# OSP_Carrier_V7_Release_DJB.net
KiCad netlist of a schematic drawn in Altium Designer
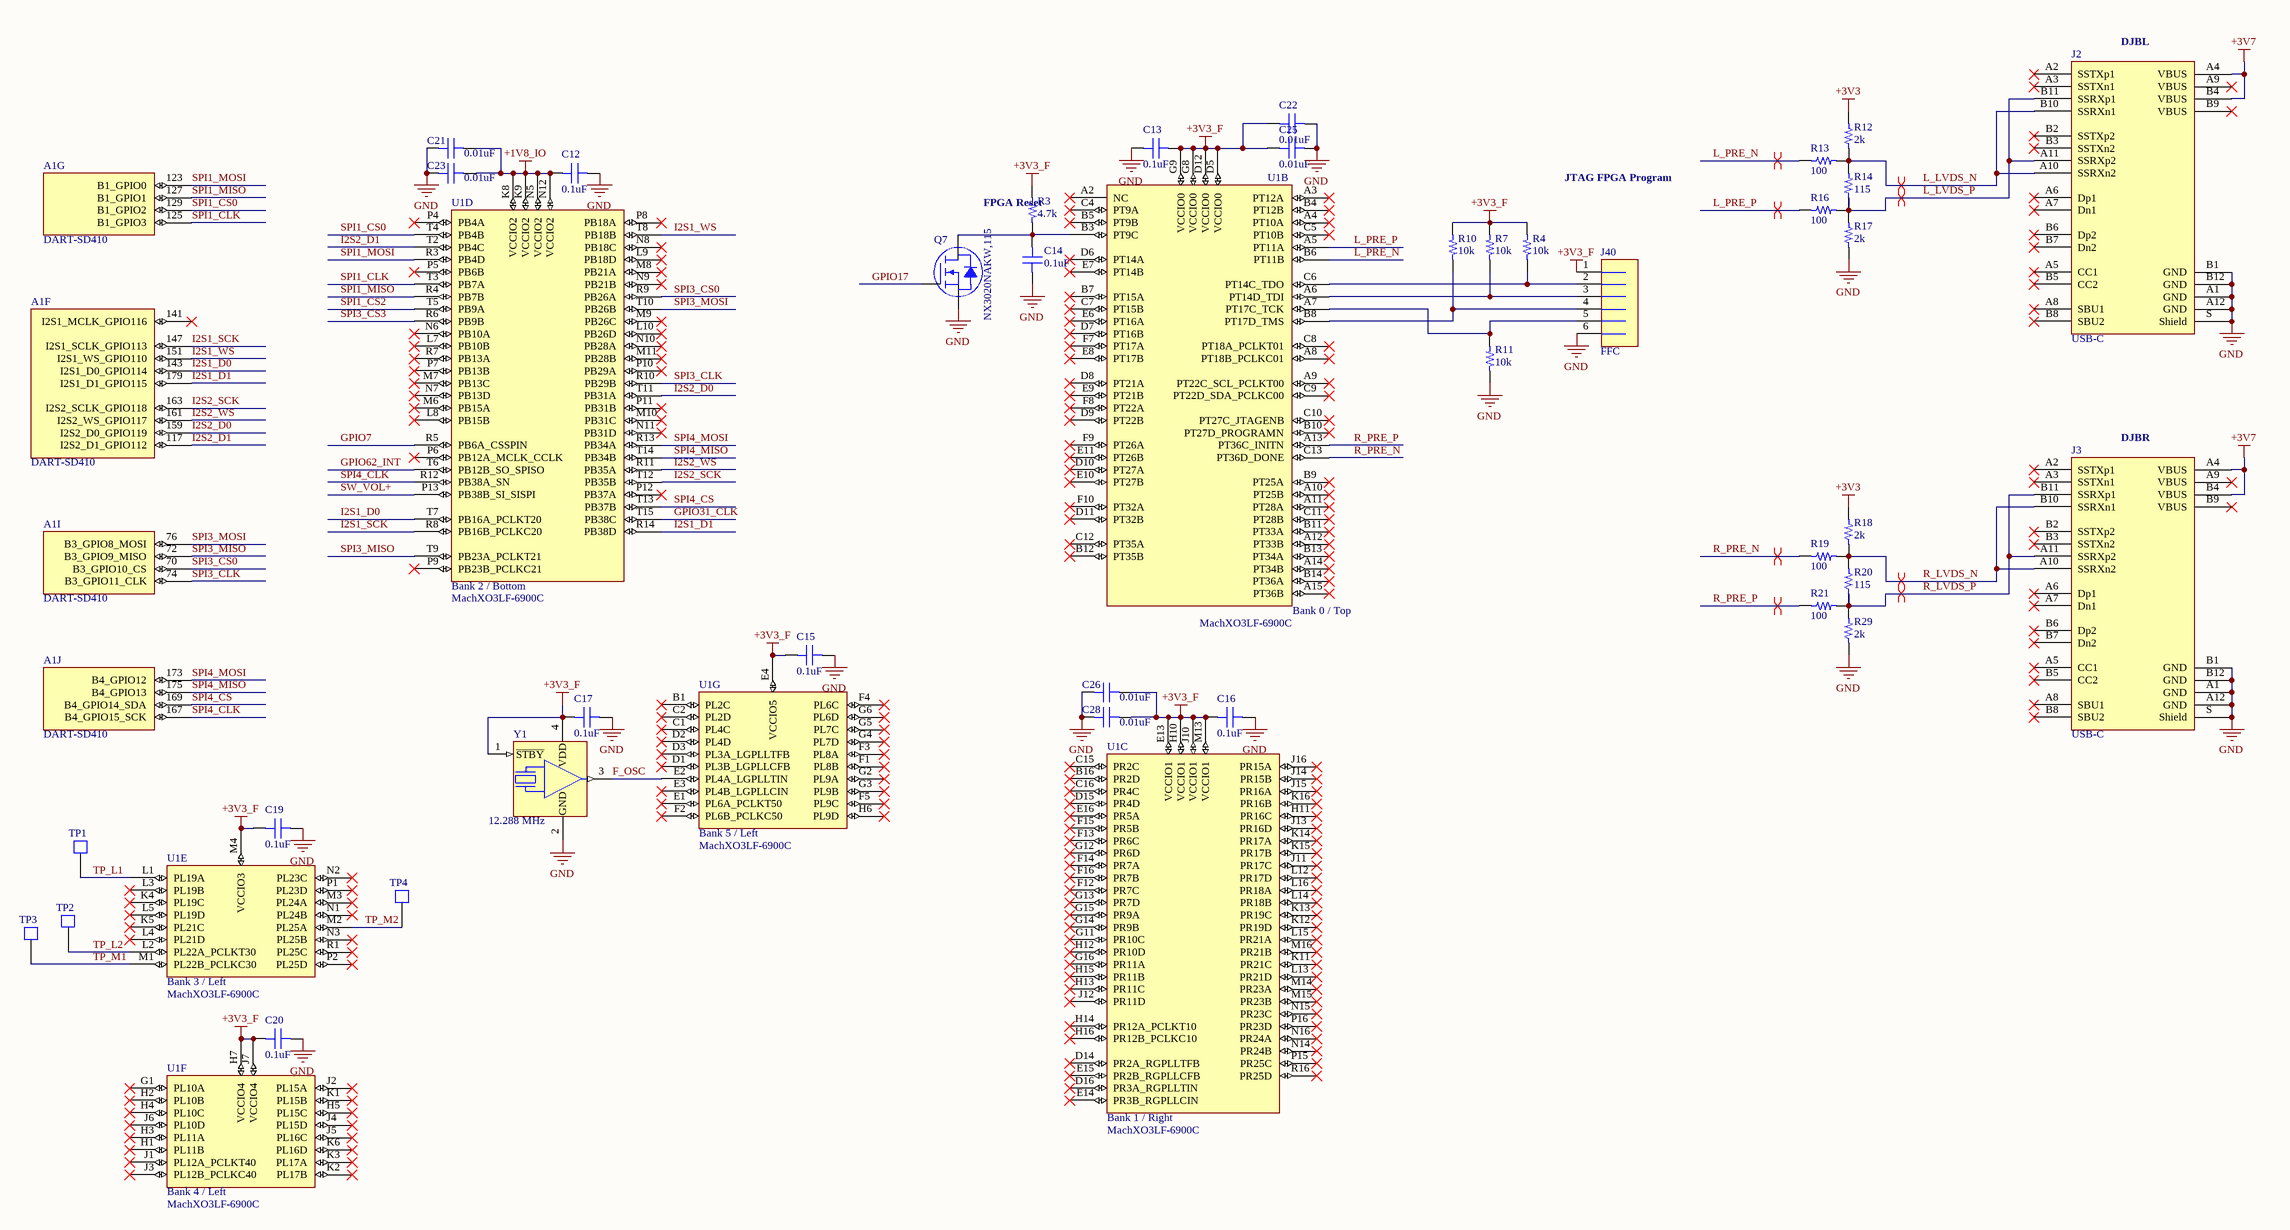
[diagram p0: OSP_Carrier_V7_Release_DJB.SchDoc]

(export (version "E")
  (design (tool "Eeschema 10.0.6"))
  (components
    (comp (ref "A1")
      (value "DART-SD410")
      (footprint "DART-SD410")
      (description "Variscite DART-SD410 System on Module")
      (libsource (lib "DART-SD410") (part "DART-SD410"))
    )
    (comp (ref "C12")
      (value "0.1uF")
      (footprint "CAP 0402/1005")
      (description "CAP CER 0.1UF 50V X7R 0402")
      (fields
        (field (name "PART NUMBER") "C1005X7R1H104K050BB")
        (field (name "MANUFACTURER") "TDK Corporation")
      )
      (libsource (lib "Celestial Library Database") (part "Capacitor"))
    )
    (comp (ref "C13")
      (value "0.1uF")
      (footprint "CAP 0402/1005")
      (description "CAP CER 0.1UF 50V X7R 0402")
      (fields
        (field (name "PART NUMBER") "C1005X7R1H104K050BB")
        (field (name "MANUFACTURER") "TDK Corporation")
      )
      (libsource (lib "Celestial Library Database") (part "Capacitor"))
    )
    (comp (ref "C14")
      (value "0.1uF")
      (footprint "CAP 0402/1005")
      (description "CAP CER 0.1UF 50V X7R 0402")
      (fields
        (field (name "PART NUMBER") "C1005X7R1H104K050BB")
        (field (name "MANUFACTURER") "TDK Corporation")
      )
      (libsource (lib "Celestial Library Database") (part "Capacitor"))
    )
    (comp (ref "C15")
      (value "0.1uF")
      (footprint "CAP 0402/1005")
      (description "CAP CER 0.1UF 50V X7R 0402")
      (fields
        (field (name "PART NUMBER") "C1005X7R1H104K050BB")
        (field (name "MANUFACTURER") "TDK Corporation")
      )
      (libsource (lib "Celestial Library Database") (part "Capacitor"))
    )
    (comp (ref "C16")
      (value "0.1uF")
      (footprint "CAP 0402/1005")
      (description "CAP CER 0.1UF 50V X7R 0402")
      (fields
        (field (name "PART NUMBER") "C1005X7R1H104K050BB")
        (field (name "MANUFACTURER") "TDK Corporation")
      )
      (libsource (lib "Celestial Library Database") (part "Capacitor"))
    )
    (comp (ref "C17")
      (value "0.1uF")
      (footprint "CAP 0402/1005")
      (description "CAP CER 0.1UF 50V X7R 0402")
      (fields
        (field (name "PART NUMBER") "C1005X7R1H104K050BB")
        (field (name "MANUFACTURER") "TDK Corporation")
      )
      (libsource (lib "Celestial Library Database") (part "Capacitor"))
    )
    (comp (ref "C19")
      (value "0.1uF")
      (footprint "CAP 0402/1005")
      (description "CAP CER 0.1UF 50V X7R 0402")
      (fields
        (field (name "PART NUMBER") "C1005X7R1H104K050BB")
        (field (name "MANUFACTURER") "TDK Corporation")
      )
      (libsource (lib "Celestial Library Database") (part "Capacitor"))
    )
    (comp (ref "C20")
      (value "0.1uF")
      (footprint "CAP 0402/1005")
      (description "CAP CER 0.1UF 50V X7R 0402")
      (fields
        (field (name "PART NUMBER") "C1005X7R1H104K050BB")
        (field (name "MANUFACTURER") "TDK Corporation")
      )
      (libsource (lib "Celestial Library Database") (part "Capacitor"))
    )
    (comp (ref "C21")
      (value "0.01uF")
      (footprint "CAP 0402/1005")
      (description "CAP CER 10000PF 25V X7R 0402")
      (fields (field (name "PART NUMBER") "CC0402KRX7R8BB103") (field (name "MANUFACTURER") "Yageo"))
      (libsource (lib "Celestial Library Database") (part "Capacitor"))
    )
    (comp (ref "C22")
      (value "0.01uF")
      (footprint "CAP 0402/1005")
      (description "CAP CER 10000PF 25V X7R 0402")
      (fields (field (name "PART NUMBER") "CC0402KRX7R8BB103") (field (name "MANUFACTURER") "Yageo"))
      (libsource (lib "Celestial Library Database") (part "Capacitor"))
    )
    (comp (ref "C23")
      (value "0.01uF")
      (footprint "CAP 0402/1005")
      (description "CAP CER 10000PF 25V X7R 0402")
      (fields (field (name "PART NUMBER") "CC0402KRX7R8BB103") (field (name "MANUFACTURER") "Yageo"))
      (libsource (lib "Celestial Library Database") (part "Capacitor"))
    )
    (comp (ref "C25")
      (value "0.01uF")
      (footprint "CAP 0402/1005")
      (description "CAP CER 10000PF 25V X7R 0402")
      (fields (field (name "PART NUMBER") "CC0402KRX7R8BB103") (field (name "MANUFACTURER") "Yageo"))
      (libsource (lib "Celestial Library Database") (part "Capacitor"))
    )
    (comp (ref "C26")
      (value "0.01uF")
      (footprint "CAP 0402/1005")
      (description "CAP CER 10000PF 25V X7R 0402")
      (fields (field (name "PART NUMBER") "CC0402KRX7R8BB103") (field (name "MANUFACTURER") "Yageo"))
      (libsource (lib "Celestial Library Database") (part "Capacitor"))
    )
    (comp (ref "C28")
      (value "0.01uF")
      (footprint "CAP 0402/1005")
      (description "CAP CER 10000PF 25V X7R 0402")
      (fields (field (name "PART NUMBER") "CC0402KRX7R8BB103") (field (name "MANUFACTURER") "Yageo"))
      (libsource (lib "Celestial Library Database") (part "Capacitor"))
    )
    (comp (ref "J2")
      (value "USB-C")
      (footprint "TE_USB-C_2129691-1")
      (description "TE 2129691-1 USB-C Socket")
      (libsource (lib "OSP_Symbols") (part "TE_USB_C_2129691-1"))
    )
    (comp (ref "J3")
      (value "USB-C")
      (footprint "TE_USB-C_2129691-1")
      (description "TE 2129691-1 USB-C Socket")
      (libsource (lib "OSP_Symbols") (part "TE_USB_C_2129691-1"))
    )
    (comp (ref "J40")
      (value "FFC")
      (footprint "AMPHENOL_HFW6R-1STE1LF")
      (description "Amphenol HFW6R-1STE1LF 6-pin flat flexible cable connector")
      (libsource (lib "OSP_Symbols") (part "AMPHENOL_HFW6R-1STE1LF"))
    )
    (comp (ref "Q7")
      (value "NX3020NAKW,115")
      (footprint "NXP SOT-323-3")
      (description "MOSFET N-CH 30V 180MA SOT323")
      (libsource (lib "Celestial Library Database") (part "NXP MOSFET N-CH SOT-23-3"))
    )
    (comp (ref "R3")
      (value "4.7k")
      (footprint "RES 0402/1005")
      (description "RES SMD 4.7K OHM 1% 1/10W 0402")
      (fields
        (field (name "PART NUMBER") "ERJ-2RKF4701X")
        (field (name "MANUFACTURER") "Panasonic Electronic Components")
      )
      (libsource (lib "Celestial Library Database") (part "Resistor"))
    )
    (comp (ref "R4")
      (value "10k")
      (footprint "RES 0402/1005")
      (description "RES SMD 10K OHM 1% 1/10W 0402")
      (fields
        (field (name "PART NUMBER") "ERJ-2RKF1002X")
        (field (name "MANUFACTURER") "Panasonic Electronic Components")
      )
      (libsource (lib "Celestial Library Database") (part "Resistor"))
    )
    (comp (ref "R7")
      (value "10k")
      (footprint "RES 0402/1005")
      (description "RES SMD 10K OHM 1% 1/10W 0402")
      (fields
        (field (name "PART NUMBER") "ERJ-2RKF1002X")
        (field (name "MANUFACTURER") "Panasonic Electronic Components")
      )
      (libsource (lib "Celestial Library Database") (part "Resistor"))
    )
    (comp (ref "R10")
      (value "10k")
      (footprint "RES 0402/1005")
      (description "RES SMD 10K OHM 1% 1/10W 0402")
      (fields
        (field (name "PART NUMBER") "ERJ-2RKF1002X")
        (field (name "MANUFACTURER") "Panasonic Electronic Components")
      )
      (libsource (lib "Celestial Library Database") (part "Resistor"))
    )
    (comp (ref "R11")
      (value "10k")
      (footprint "RES 0402/1005")
      (description "RES SMD 10K OHM 1% 1/10W 0402")
      (fields
        (field (name "PART NUMBER") "ERJ-2RKF1002X")
        (field (name "MANUFACTURER") "Panasonic Electronic Components")
      )
      (libsource (lib "Celestial Library Database") (part "Resistor"))
    )
    (comp (ref "R12")
      (value "2k")
      (footprint "RES 0402/1005")
      (description "RES SMD 2K OHM 1% 1/10W 0402")
      (fields
        (field (name "PART NUMBER") "ERJ-2RKF2001X")
        (field (name "MANUFACTURER") "Panasonic Electronic Components")
      )
      (libsource (lib "Celestial Library Database") (part "Resistor"))
    )
    (comp (ref "R13")
      (value "100")
      (footprint "RES 0402/1005")
      (description "RES SMD 100 OHM 1% 1/10W 0402")
      (fields
        (field (name "PART NUMBER") "ERJ-2RKF1000X")
        (field (name "MANUFACTURER") "Panasonic Electronic Components")
      )
      (libsource (lib "Celestial Library Database") (part "Resistor"))
    )
    (comp (ref "R14")
      (value "115")
      (footprint "RES 0402/1005")
      (description "RES SMD 115 OHM 1% 1/10W 0402")
      (fields
        (field (name "PART NUMBER") "ERJ-2RKF1150X")
        (field (name "MANUFACTURER") "Panasonic Electronic Components")
      )
      (libsource (lib "Celestial Library Database") (part "Resistor"))
    )
    (comp (ref "R16")
      (value "100")
      (footprint "RES 0402/1005")
      (description "RES SMD 100 OHM 1% 1/10W 0402")
      (fields
        (field (name "PART NUMBER") "ERJ-2RKF1000X")
        (field (name "MANUFACTURER") "Panasonic Electronic Components")
      )
      (libsource (lib "Celestial Library Database") (part "Resistor"))
    )
    (comp (ref "R17")
      (value "2k")
      (footprint "RES 0402/1005")
      (description "RES SMD 2K OHM 1% 1/10W 0402")
      (fields
        (field (name "PART NUMBER") "ERJ-2RKF2001X")
        (field (name "MANUFACTURER") "Panasonic Electronic Components")
      )
      (libsource (lib "Celestial Library Database") (part "Resistor"))
    )
    (comp (ref "R18")
      (value "2k")
      (footprint "RES 0402/1005")
      (description "RES SMD 2K OHM 1% 1/10W 0402")
      (fields
        (field (name "PART NUMBER") "ERJ-2RKF2001X")
        (field (name "MANUFACTURER") "Panasonic Electronic Components")
      )
      (libsource (lib "Celestial Library Database") (part "Resistor"))
    )
    (comp (ref "R19")
      (value "100")
      (footprint "RES 0402/1005")
      (description "RES SMD 100 OHM 1% 1/10W 0402")
      (fields
        (field (name "PART NUMBER") "ERJ-2RKF1000X")
        (field (name "MANUFACTURER") "Panasonic Electronic Components")
      )
      (libsource (lib "Celestial Library Database") (part "Resistor"))
    )
    (comp (ref "R20")
      (value "115")
      (footprint "RES 0402/1005")
      (description "RES SMD 115 OHM 1% 1/10W 0402")
      (fields
        (field (name "PART NUMBER") "ERJ-2RKF1150X")
        (field (name "MANUFACTURER") "Panasonic Electronic Components")
      )
      (libsource (lib "Celestial Library Database") (part "Resistor"))
    )
    (comp (ref "R21")
      (value "100")
      (footprint "RES 0402/1005")
      (description "RES SMD 100 OHM 1% 1/10W 0402")
      (fields
        (field (name "PART NUMBER") "ERJ-2RKF1000X")
        (field (name "MANUFACTURER") "Panasonic Electronic Components")
      )
      (libsource (lib "Celestial Library Database") (part "Resistor"))
    )
    (comp (ref "R29")
      (value "2k")
      (footprint "RES 0402/1005")
      (description "RES SMD 2K OHM 1% 1/10W 0402")
      (fields
        (field (name "PART NUMBER") "ERJ-2RKF2001X")
        (field (name "MANUFACTURER") "Panasonic Electronic Components")
      )
      (libsource (lib "Celestial Library Database") (part "Resistor"))
    )
    (comp (ref "TP1")
      (value "TP_SMD_1MM_SQ")
      (footprint "TP_SMD_1MM_SQ")
      (description "1mm Square SMD Test Point")
      (libsource (lib "OSP_Symbols") (part "TP_SMD_1MM_SQ"))
    )
    (comp (ref "TP2")
      (value "TP_SMD_1MM_SQ")
      (footprint "TP_SMD_1MM_SQ")
      (description "1mm Square SMD Test Point")
      (libsource (lib "OSP_Symbols") (part "TP_SMD_1MM_SQ"))
    )
    (comp (ref "TP3")
      (value "TP_SMD_1MM_SQ")
      (footprint "TP_SMD_1MM_SQ")
      (description "1mm Square SMD Test Point")
      (libsource (lib "OSP_Symbols") (part "TP_SMD_1MM_SQ"))
    )
    (comp (ref "TP4")
      (value "TP_SMD_1MM_SQ")
      (footprint "TP_SMD_1MM_SQ")
      (description "1mm Square SMD Test Point")
      (libsource (lib "OSP_Symbols") (part "TP_SMD_1MM_SQ"))
    )
    (comp (ref "U1")
      (value "MachXO3LF-6900C")
      (footprint "LCMXO3_caBGA_BG256")
      (description "Lattice MachXO3LF-6900C-5BG256C FPGA")
      (libsource (lib "OSP_Symbols") (part "LCMXO3LF-6900C-XBG256X"))
    )
    (comp (ref "Y1")
      (value "12.288 MHz")
      (footprint "OSC_2.5x2.0mm")
      (description "Microchip 12.288 MHz SMD MEMS Oscillator")
      (libsource (lib "OSP_Symbols") (part "MC_DSC1033DI2-012.2880"))
    )
  )
  (nets
    (net (code "1") (name "+1V8_IO") (class "Default")
      (node (ref "C12") (pin "2") (pinfunction "2_2") (pintype "passive"))
      (node (ref "C21") (pin "1") (pinfunction "1_1") (pintype "passive"))
      (node (ref "C23") (pin "1") (pinfunction "1_1") (pintype "passive"))
      (node (ref "U1") (pin "K8") (pinfunction "VCCIO2_K8") (pintype "bidirectional"))
      (node (ref "U1") (pin "K9") (pinfunction "VCCIO2_K9") (pintype "bidirectional"))
      (node (ref "U1") (pin "N12") (pinfunction "VCCIO2_N12") (pintype "bidirectional"))
      (node (ref "U1") (pin "N5") (pinfunction "VCCIO2_N5") (pintype "bidirectional"))
    )
    (net (code "2") (name "+3V3") (class "Default")
      (node (ref "R12") (pin "2") (pinfunction "2_2") (pintype "passive"))
      (node (ref "R18") (pin "2") (pinfunction "2_2") (pintype "passive"))
    )
    (net (code "3") (name "+3V3_F") (class "Default")
      (node (ref "C13") (pin "2") (pinfunction "2_2") (pintype "passive"))
      (node (ref "C15") (pin "2") (pinfunction "2_2") (pintype "passive"))
      (node (ref "C16") (pin "2") (pinfunction "2_2") (pintype "passive"))
      (node (ref "C17") (pin "2") (pinfunction "2_2") (pintype "passive"))
      (node (ref "C19") (pin "2") (pinfunction "2_2") (pintype "passive"))
      (node (ref "C20") (pin "2") (pinfunction "2_2") (pintype "passive"))
      (node (ref "C22") (pin "1") (pinfunction "1_1") (pintype "passive"))
      (node (ref "C25") (pin "1") (pinfunction "1_1") (pintype "passive"))
      (node (ref "C26") (pin "1") (pinfunction "1_1") (pintype "passive"))
      (node (ref "C28") (pin "1") (pinfunction "1_1") (pintype "passive"))
      (node (ref "J40") (pin "1") (pintype "passive"))
      (node (ref "R10") (pin "2") (pinfunction "2_2") (pintype "passive"))
      (node (ref "R3") (pin "2") (pinfunction "2_2") (pintype "passive"))
      (node (ref "R4") (pin "2") (pinfunction "2_2") (pintype "passive"))
      (node (ref "R7") (pin "2") (pinfunction "2_2") (pintype "passive"))
      (node (ref "U1") (pin "D12") (pinfunction "VCCIO0_D12") (pintype "bidirectional"))
      (node (ref "U1") (pin "D5") (pinfunction "VCCIO0_D5") (pintype "bidirectional"))
      (node (ref "U1") (pin "E13") (pinfunction "VCCIO1_E13") (pintype "bidirectional"))
      (node (ref "U1") (pin "E4") (pinfunction "VCCIO5_E4") (pintype "bidirectional"))
      (node (ref "U1") (pin "G8") (pinfunction "VCCIO0_G8") (pintype "bidirectional"))
      (node (ref "U1") (pin "G9") (pinfunction "VCCIO0_G9") (pintype "bidirectional"))
      (node (ref "U1") (pin "H10") (pinfunction "VCCIO1_H10") (pintype "bidirectional"))
      (node (ref "U1") (pin "H7") (pinfunction "VCCIO4_H7") (pintype "bidirectional"))
      (node (ref "U1") (pin "J10") (pinfunction "VCCIO1_J10") (pintype "bidirectional"))
      (node (ref "U1") (pin "J7") (pinfunction "VCCIO4_J7") (pintype "bidirectional"))
      (node (ref "U1") (pin "M13") (pinfunction "VCCIO1_M13") (pintype "bidirectional"))
      (node (ref "U1") (pin "M4") (pinfunction "VCCIO3_M4") (pintype "bidirectional"))
      (node (ref "Y1") (pin "1") (pinfunction "~{STBY}_1") (pintype "input"))
      (node (ref "Y1") (pin "4") (pinfunction "VDD_4") (pintype "power_in"))
    )
    (net (code "4") (name "+3V7") (class "Default")
      (node (ref "J2") (pin "A4") (pinfunction "VBUS_A4") (pintype "passive"))
      (node (ref "J2") (pin "B4") (pinfunction "VBUS_B4") (pintype "passive"))
      (node (ref "J3") (pin "A4") (pinfunction "VBUS_A4") (pintype "passive"))
      (node (ref "J3") (pin "B4") (pinfunction "VBUS_B4") (pintype "passive"))
    )
    (net (code "5") (name "/F_OSC") (class "Default")
      (node (ref "U1") (pin "E2") (pinfunction "PL4A_LGPLLTIN_E2") (pintype "bidirectional"))
      (node (ref "Y1") (pin "3") (pinfunction "OUT_3") (pintype "output"))
    )
    (net (code "6") (name "/GPIO7") (class "Default")
      (node (ref "U1") (pin "R5") (pinfunction "PB6A_CSSPIN_R5") (pintype "bidirectional"))
    )
    (net (code "7") (name "/GPIO17") (class "Default")
      (node (ref "Q7") (pin "1") (pinfunction "G_1") (pintype "passive"))
    )
    (net (code "8") (name "/GPIO31_CLK") (class "Default")
      (node (ref "U1") (pin "T15") (pinfunction "PB38C_T15") (pintype "bidirectional"))
    )
    (net (code "9") (name "/GPIO62_INT") (class "Default")
      (node (ref "U1") (pin "T6") (pinfunction "PB12B_SO_SPISO_T6") (pintype "bidirectional"))
    )
    (net (code "10") (name "/I2S1_D0") (class "Default")
      (node (ref "A1") (pin "143") (pinfunction "I2S1_D0_GPIO114_143") (pintype "bidirectional"))
      (node (ref "U1") (pin "T7") (pinfunction "PB16A_PCLKT20_T7") (pintype "bidirectional"))
    )
    (net (code "11") (name "/I2S1_D1") (class "Default")
      (node (ref "A1") (pin "179") (pinfunction "I2S1_D1_GPIO115_179") (pintype "bidirectional"))
      (node (ref "U1") (pin "R14") (pinfunction "PB38D_R14") (pintype "bidirectional"))
    )
    (net (code "12") (name "/I2S1_SCK") (class "Default")
      (node (ref "A1") (pin "147") (pinfunction "I2S1_SCLK_GPIO113_147") (pintype "bidirectional"))
      (node (ref "U1") (pin "R8") (pinfunction "PB16B_PCLKC20_R8") (pintype "bidirectional"))
    )
    (net (code "13") (name "/I2S1_WS") (class "Default")
      (node (ref "A1") (pin "151") (pinfunction "I2S1_WS_GPIO110_151") (pintype "bidirectional"))
      (node (ref "U1") (pin "T8") (pinfunction "PB18B_T8") (pintype "bidirectional"))
    )
    (net (code "14") (name "/I2S2_D0") (class "Default")
      (node (ref "A1") (pin "159") (pinfunction "I2S2_D0_GPIO119_159") (pintype "bidirectional"))
      (node (ref "U1") (pin "T11") (pinfunction "PB31A_T11") (pintype "bidirectional"))
    )
    (net (code "15") (name "/I2S2_D1") (class "Default")
      (node (ref "A1") (pin "117") (pinfunction "I2S2_D1_GPIO112_117") (pintype "bidirectional"))
      (node (ref "U1") (pin "T2") (pinfunction "PB4C_T2") (pintype "bidirectional"))
    )
    (net (code "16") (name "/I2S2_SCK") (class "Default")
      (node (ref "A1") (pin "163") (pinfunction "I2S2_SCLK_GPIO118_163") (pintype "bidirectional"))
      (node (ref "U1") (pin "T12") (pinfunction "PB35B_T12") (pintype "bidirectional"))
    )
    (net (code "17") (name "/I2S2_WS") (class "Default")
      (node (ref "A1") (pin "161") (pinfunction "I2S2_WS_GPIO117_161") (pintype "bidirectional"))
      (node (ref "U1") (pin "R11") (pinfunction "PB35A_R11") (pintype "bidirectional"))
    )
    (net (code "18") (name "/L_LVDS_N") (class "Default")
      (node (ref "J2") (pin "A10") (pinfunction "SSRXn2_A10") (pintype "passive"))
      (node (ref "J2") (pin "B10") (pinfunction "SSRXn1_B10") (pintype "passive"))
      (node (ref "R12") (pin "1") (pinfunction "1_1") (pintype "passive"))
      (node (ref "R13") (pin "2") (pinfunction "2_2") (pintype "passive"))
      (node (ref "R14") (pin "2") (pinfunction "2_2") (pintype "passive"))
    )
    (net (code "19") (name "/L_LVDS_P") (class "Default")
      (node (ref "J2") (pin "A11") (pinfunction "SSRXp2_A11") (pintype "passive"))
      (node (ref "J2") (pin "B11") (pinfunction "SSRXp1_B11") (pintype "passive"))
      (node (ref "R14") (pin "1") (pinfunction "1_1") (pintype "passive"))
      (node (ref "R16") (pin "2") (pinfunction "2_2") (pintype "passive"))
      (node (ref "R17") (pin "2") (pinfunction "2_2") (pintype "passive"))
    )
    (net (code "20") (name "/L_PRE_N") (class "Default")
      (node (ref "R13") (pin "1") (pinfunction "1_1") (pintype "passive"))
      (node (ref "U1") (pin "B6") (pinfunction "PT11B_B6") (pintype "bidirectional"))
    )
    (net (code "21") (name "/L_PRE_P") (class "Default")
      (node (ref "R16") (pin "1") (pinfunction "1_1") (pintype "passive"))
      (node (ref "U1") (pin "A5") (pinfunction "PT11A_A5") (pintype "bidirectional"))
    )
    (net (code "22") (name "/R_LVDS_N") (class "Default")
      (node (ref "J3") (pin "A10") (pinfunction "SSRXn2_A10") (pintype "passive"))
      (node (ref "J3") (pin "B10") (pinfunction "SSRXn1_B10") (pintype "passive"))
      (node (ref "R18") (pin "1") (pinfunction "1_1") (pintype "passive"))
      (node (ref "R19") (pin "2") (pinfunction "2_2") (pintype "passive"))
      (node (ref "R20") (pin "2") (pinfunction "2_2") (pintype "passive"))
    )
    (net (code "23") (name "/R_LVDS_P") (class "Default")
      (node (ref "J3") (pin "A11") (pinfunction "SSRXp2_A11") (pintype "passive"))
      (node (ref "J3") (pin "B11") (pinfunction "SSRXp1_B11") (pintype "passive"))
      (node (ref "R20") (pin "1") (pinfunction "1_1") (pintype "passive"))
      (node (ref "R21") (pin "2") (pinfunction "2_2") (pintype "passive"))
      (node (ref "R29") (pin "2") (pinfunction "2_2") (pintype "passive"))
    )
    (net (code "24") (name "/R_PRE_N") (class "Default")
      (node (ref "R19") (pin "1") (pinfunction "1_1") (pintype "passive"))
      (node (ref "U1") (pin "C13") (pinfunction "PT36D_DONE_C13") (pintype "bidirectional"))
    )
    (net (code "25") (name "/R_PRE_P") (class "Default")
      (node (ref "R21") (pin "1") (pinfunction "1_1") (pintype "passive"))
      (node (ref "U1") (pin "A13") (pinfunction "PT36C_INITN_A13") (pintype "bidirectional"))
    )
    (net (code "26") (name "/SPI1_CLK") (class "Default")
      (node (ref "A1") (pin "125") (pinfunction "B1_GPIO3_125") (pintype "bidirectional"))
      (node (ref "U1") (pin "T3") (pinfunction "PB7A_T3") (pintype "bidirectional"))
    )
    (net (code "27") (name "/SPI1_CS0") (class "Default")
      (node (ref "A1") (pin "129") (pinfunction "B1_GPIO2_129") (pintype "bidirectional"))
      (node (ref "U1") (pin "T4") (pinfunction "PB4B_T4") (pintype "bidirectional"))
    )
    (net (code "28") (name "/SPI1_CS2") (class "Default")
      (node (ref "U1") (pin "T5") (pinfunction "PB9A_T5") (pintype "bidirectional"))
    )
    (net (code "29") (name "/SPI1_MISO") (class "Default")
      (node (ref "A1") (pin "127") (pinfunction "B1_GPIO1_127") (pintype "bidirectional"))
      (node (ref "U1") (pin "R4") (pinfunction "PB7B_R4") (pintype "bidirectional"))
    )
    (net (code "30") (name "/SPI1_MOSI") (class "Default")
      (node (ref "A1") (pin "123") (pinfunction "B1_GPIO0_123") (pintype "bidirectional"))
      (node (ref "U1") (pin "R3") (pinfunction "PB4D_R3") (pintype "bidirectional"))
    )
    (net (code "31") (name "/SPI3_CLK") (class "Default")
      (node (ref "A1") (pin "74") (pinfunction "B3_GPIO11_CLK_74") (pintype "bidirectional"))
      (node (ref "U1") (pin "R10") (pinfunction "PB29B_R10") (pintype "bidirectional"))
    )
    (net (code "32") (name "/SPI3_CS0") (class "Default")
      (node (ref "A1") (pin "70") (pinfunction "B3_GPIO10_CS_70") (pintype "bidirectional"))
      (node (ref "U1") (pin "R9") (pinfunction "PB26A_R9") (pintype "bidirectional"))
    )
    (net (code "33") (name "/SPI3_CS3") (class "Default")
      (node (ref "U1") (pin "R6") (pinfunction "PB9B_R6") (pintype "bidirectional"))
    )
    (net (code "34") (name "/SPI3_MISO") (class "Default")
      (node (ref "A1") (pin "72") (pinfunction "B3_GPIO9_MISO_72") (pintype "bidirectional"))
      (node (ref "U1") (pin "T9") (pinfunction "PB23A_PCLKT21_T9") (pintype "bidirectional"))
    )
    (net (code "35") (name "/SPI3_MOSI") (class "Default")
      (node (ref "A1") (pin "76") (pinfunction "B3_GPIO8_MOSI_76") (pintype "bidirectional"))
      (node (ref "U1") (pin "T10") (pinfunction "PB26B_T10") (pintype "bidirectional"))
    )
    (net (code "36") (name "/SPI4_CLK") (class "Default")
      (node (ref "A1") (pin "167") (pinfunction "B4_GPIO15_SCK_167") (pintype "bidirectional"))
      (node (ref "U1") (pin "R12") (pinfunction "PB38A_SN_R12") (pintype "bidirectional"))
    )
    (net (code "37") (name "/SPI4_CS") (class "Default")
      (node (ref "A1") (pin "169") (pinfunction "B4_GPIO14_SDA_169") (pintype "bidirectional"))
      (node (ref "U1") (pin "T13") (pinfunction "PB37B_T13") (pintype "bidirectional"))
    )
    (net (code "38") (name "/SPI4_MISO") (class "Default")
      (node (ref "A1") (pin "175") (pinfunction "B4_GPIO13_175") (pintype "bidirectional"))
      (node (ref "U1") (pin "T14") (pinfunction "PB34B_T14") (pintype "bidirectional"))
    )
    (net (code "39") (name "/SPI4_MOSI") (class "Default")
      (node (ref "A1") (pin "173") (pinfunction "B4_GPIO12_173") (pintype "bidirectional"))
      (node (ref "U1") (pin "R13") (pinfunction "PB34A_R13") (pintype "bidirectional"))
    )
    (net (code "40") (name "/SW_VOL+") (class "Default")
      (node (ref "U1") (pin "P13") (pinfunction "PB38B_SI_SISPI_P13") (pintype "bidirectional"))
    )
    (net (code "41") (name "/TP_L1") (class "Default")
      (node (ref "TP1") (pin "1") (pintype "passive"))
      (node (ref "U1") (pin "L1") (pinfunction "PL19A_L1") (pintype "bidirectional"))
    )
    (net (code "42") (name "/TP_L2") (class "Default")
      (node (ref "TP2") (pin "1") (pintype "passive"))
      (node (ref "U1") (pin "L2") (pinfunction "PL22A_PCLKT30_L2") (pintype "bidirectional"))
    )
    (net (code "43") (name "/TP_M1") (class "Default")
      (node (ref "TP3") (pin "1") (pintype "passive"))
      (node (ref "U1") (pin "M1") (pinfunction "PL22B_PCLKC30_M1") (pintype "bidirectional"))
    )
    (net (code "44") (name "/TP_M2") (class "Default")
      (node (ref "TP4") (pin "1") (pintype "passive"))
      (node (ref "U1") (pin "M2") (pinfunction "PL25A_M2") (pintype "bidirectional"))
    )
    (net (code "45") (name "GND") (class "Default")
      (node (ref "C12") (pin "1") (pinfunction "1_1") (pintype "passive"))
      (node (ref "C13") (pin "1") (pinfunction "1_1") (pintype "passive"))
      (node (ref "C14") (pin "2") (pinfunction "2_2") (pintype "passive"))
      (node (ref "C15") (pin "1") (pinfunction "1_1") (pintype "passive"))
      (node (ref "C16") (pin "1") (pinfunction "1_1") (pintype "passive"))
      (node (ref "C17") (pin "1") (pinfunction "1_1") (pintype "passive"))
      (node (ref "C19") (pin "1") (pinfunction "1_1") (pintype "passive"))
      (node (ref "C20") (pin "1") (pinfunction "1_1") (pintype "passive"))
      (node (ref "C21") (pin "2") (pinfunction "2_2") (pintype "passive"))
      (node (ref "C22") (pin "2") (pinfunction "2_2") (pintype "passive"))
      (node (ref "C23") (pin "2") (pinfunction "2_2") (pintype "passive"))
      (node (ref "C25") (pin "2") (pinfunction "2_2") (pintype "passive"))
      (node (ref "C26") (pin "2") (pinfunction "2_2") (pintype "passive"))
      (node (ref "C28") (pin "2") (pinfunction "2_2") (pintype "passive"))
      (node (ref "J2") (pin "A1") (pinfunction "GND_A1") (pintype "passive"))
      (node (ref "J2") (pin "A12") (pinfunction "GND_A12") (pintype "passive"))
      (node (ref "J2") (pin "B1") (pinfunction "GND_B1") (pintype "passive"))
      (node (ref "J2") (pin "B12") (pinfunction "GND_B12") (pintype "passive"))
      (node (ref "J2") (pin "S") (pinfunction "Shield_S") (pintype "passive"))
      (node (ref "J3") (pin "A1") (pinfunction "GND_A1") (pintype "passive"))
      (node (ref "J3") (pin "A12") (pinfunction "GND_A12") (pintype "passive"))
      (node (ref "J3") (pin "B1") (pinfunction "GND_B1") (pintype "passive"))
      (node (ref "J3") (pin "B12") (pinfunction "GND_B12") (pintype "passive"))
      (node (ref "J3") (pin "S") (pinfunction "Shield_S") (pintype "passive"))
      (node (ref "J40") (pin "6") (pintype "passive"))
      (node (ref "Q7") (pin "3") (pinfunction "S_3") (pintype "passive"))
      (node (ref "R11") (pin "1") (pinfunction "1_1") (pintype "passive"))
      (node (ref "R17") (pin "1") (pinfunction "1_1") (pintype "passive"))
      (node (ref "R29") (pin "1") (pinfunction "1_1") (pintype "passive"))
      (node (ref "Y1") (pin "2") (pinfunction "GND_2") (pintype "power_in"))
    )
    (net (code "46") (name "Net-(Q7-D)") (class "Default")
      (node (ref "C14") (pin "1") (pinfunction "1_1") (pintype "passive"))
      (node (ref "Q7") (pin "2") (pinfunction "D_2") (pintype "passive"))
      (node (ref "R3") (pin "1") (pinfunction "1_1") (pintype "passive"))
      (node (ref "U1") (pin "B3") (pinfunction "PT9C_B3") (pintype "bidirectional"))
    )
    (net (code "47") (name "Net-(U1B-PT14C_TDO)") (class "Default")
      (node (ref "J40") (pin "2") (pintype "passive"))
      (node (ref "R4") (pin "1") (pinfunction "1_1") (pintype "passive"))
      (node (ref "U1") (pin "C6") (pinfunction "PT14C_TDO_C6") (pintype "bidirectional"))
    )
    (net (code "48") (name "Net-(U1B-PT14D_TDI)") (class "Default")
      (node (ref "J40") (pin "3") (pintype "passive"))
      (node (ref "R7") (pin "1") (pinfunction "1_1") (pintype "passive"))
      (node (ref "U1") (pin "A6") (pinfunction "PT14D_TDI_A6") (pintype "bidirectional"))
    )
    (net (code "49") (name "Net-(U1B-PT17C_TCK)") (class "Default")
      (node (ref "J40") (pin "5") (pintype "passive"))
      (node (ref "R11") (pin "2") (pinfunction "2_2") (pintype "passive"))
      (node (ref "U1") (pin "A7") (pinfunction "PT17C_TCK_A7") (pintype "bidirectional"))
    )
    (net (code "50") (name "Net-(U1B-PT17D_TMS)") (class "Default")
      (node (ref "J40") (pin "4") (pintype "passive"))
      (node (ref "R10") (pin "1") (pinfunction "1_1") (pintype "passive"))
      (node (ref "U1") (pin "B8") (pinfunction "PT17D_TMS_B8") (pintype "bidirectional"))
    )
    (net (code "51") (name "unconnected-(A1F-I2S1_MCLK_GPIO116-Pad141)") (class "Default")
      (node (ref "A1") (pin "141") (pinfunction "I2S1_MCLK_GPIO116_141") (pintype "bidirectional+no_connect"))
    )
    (net (code "52") (name "unconnected-(J2-CC1-PadA5)") (class "Default")
      (node (ref "J2") (pin "A5") (pinfunction "CC1_A5") (pintype "passive+no_connect"))
    )
    (net (code "53") (name "unconnected-(J2-CC2-PadB5)") (class "Default")
      (node (ref "J2") (pin "B5") (pinfunction "CC2_B5") (pintype "passive+no_connect"))
    )
    (net (code "54") (name "unconnected-(J2-Dn1-PadA7)") (class "Default")
      (node (ref "J2") (pin "A7") (pinfunction "Dn1_A7") (pintype "passive+no_connect"))
    )
    (net (code "55") (name "unconnected-(J2-Dn2-PadB7)") (class "Default")
      (node (ref "J2") (pin "B7") (pinfunction "Dn2_B7") (pintype "passive+no_connect"))
    )
    (net (code "56") (name "unconnected-(J2-Dp1-PadA6)") (class "Default")
      (node (ref "J2") (pin "A6") (pinfunction "Dp1_A6") (pintype "passive+no_connect"))
    )
    (net (code "57") (name "unconnected-(J2-Dp2-PadB6)") (class "Default")
      (node (ref "J2") (pin "B6") (pinfunction "Dp2_B6") (pintype "passive+no_connect"))
    )
    (net (code "58") (name "unconnected-(J2-SBU1-PadA8)") (class "Default")
      (node (ref "J2") (pin "A8") (pinfunction "SBU1_A8") (pintype "passive+no_connect"))
    )
    (net (code "59") (name "unconnected-(J2-SBU2-PadB8)") (class "Default")
      (node (ref "J2") (pin "B8") (pinfunction "SBU2_B8") (pintype "passive+no_connect"))
    )
    (net (code "60") (name "unconnected-(J2-SSTXn1-PadA3)") (class "Default")
      (node (ref "J2") (pin "A3") (pinfunction "SSTXn1_A3") (pintype "passive+no_connect"))
    )
    (net (code "61") (name "unconnected-(J2-SSTXn2-PadB3)") (class "Default")
      (node (ref "J2") (pin "B3") (pinfunction "SSTXn2_B3") (pintype "passive+no_connect"))
    )
    (net (code "62") (name "unconnected-(J2-SSTXp1-PadA2)") (class "Default")
      (node (ref "J2") (pin "A2") (pinfunction "SSTXp1_A2") (pintype "passive+no_connect"))
    )
    (net (code "63") (name "unconnected-(J2-SSTXp2-PadB2)") (class "Default")
      (node (ref "J2") (pin "B2") (pinfunction "SSTXp2_B2") (pintype "passive+no_connect"))
    )
    (net (code "64") (name "unconnected-(J2-VBUS-PadA9)") (class "Default")
      (node (ref "J2") (pin "A9") (pinfunction "VBUS_A9") (pintype "passive+no_connect"))
    )
    (net (code "65") (name "unconnected-(J2-VBUS-PadB9)") (class "Default")
      (node (ref "J2") (pin "B9") (pinfunction "VBUS_B9") (pintype "passive+no_connect"))
    )
    (net (code "66") (name "unconnected-(J3-CC1-PadA5)") (class "Default")
      (node (ref "J3") (pin "A5") (pinfunction "CC1_A5") (pintype "passive+no_connect"))
    )
    (net (code "67") (name "unconnected-(J3-CC2-PadB5)") (class "Default")
      (node (ref "J3") (pin "B5") (pinfunction "CC2_B5") (pintype "passive+no_connect"))
    )
    (net (code "68") (name "unconnected-(J3-Dn1-PadA7)") (class "Default")
      (node (ref "J3") (pin "A7") (pinfunction "Dn1_A7") (pintype "passive+no_connect"))
    )
    (net (code "69") (name "unconnected-(J3-Dn2-PadB7)") (class "Default")
      (node (ref "J3") (pin "B7") (pinfunction "Dn2_B7") (pintype "passive+no_connect"))
    )
    (net (code "70") (name "unconnected-(J3-Dp1-PadA6)") (class "Default")
      (node (ref "J3") (pin "A6") (pinfunction "Dp1_A6") (pintype "passive+no_connect"))
    )
    (net (code "71") (name "unconnected-(J3-Dp2-PadB6)") (class "Default")
      (node (ref "J3") (pin "B6") (pinfunction "Dp2_B6") (pintype "passive+no_connect"))
    )
    (net (code "72") (name "unconnected-(J3-SBU1-PadA8)") (class "Default")
      (node (ref "J3") (pin "A8") (pinfunction "SBU1_A8") (pintype "passive+no_connect"))
    )
    (net (code "73") (name "unconnected-(J3-SBU2-PadB8)") (class "Default")
      (node (ref "J3") (pin "B8") (pinfunction "SBU2_B8") (pintype "passive+no_connect"))
    )
    (net (code "74") (name "unconnected-(J3-SSTXn1-PadA3)") (class "Default")
      (node (ref "J3") (pin "A3") (pinfunction "SSTXn1_A3") (pintype "passive+no_connect"))
    )
    (net (code "75") (name "unconnected-(J3-SSTXn2-PadB3)") (class "Default")
      (node (ref "J3") (pin "B3") (pinfunction "SSTXn2_B3") (pintype "passive+no_connect"))
    )
    (net (code "76") (name "unconnected-(J3-SSTXp1-PadA2)") (class "Default")
      (node (ref "J3") (pin "A2") (pinfunction "SSTXp1_A2") (pintype "passive+no_connect"))
    )
    (net (code "77") (name "unconnected-(J3-SSTXp2-PadB2)") (class "Default")
      (node (ref "J3") (pin "B2") (pinfunction "SSTXp2_B2") (pintype "passive+no_connect"))
    )
    (net (code "78") (name "unconnected-(J3-VBUS-PadA9)") (class "Default")
      (node (ref "J3") (pin "A9") (pinfunction "VBUS_A9") (pintype "passive+no_connect"))
    )
    (net (code "79") (name "unconnected-(J3-VBUS-PadB9)") (class "Default")
      (node (ref "J3") (pin "B9") (pinfunction "VBUS_B9") (pintype "passive+no_connect"))
    )
    (net (code "80") (name "unconnected-(U1B-NC-PadA2)") (class "Default")
      (node (ref "U1") (pin "A2") (pinfunction "NC_A2") (pintype "passive+no_connect"))
    )
    (net (code "81") (name "unconnected-(U1B-PT9A-PadC4)") (class "Default")
      (node (ref "U1") (pin "C4") (pinfunction "PT9A_C4") (pintype "bidirectional+no_connect"))
    )
    (net (code "82") (name "unconnected-(U1B-PT9B-PadB5)") (class "Default")
      (node (ref "U1") (pin "B5") (pinfunction "PT9B_B5") (pintype "bidirectional+no_connect"))
    )
    (net (code "83") (name "unconnected-(U1B-PT10A-PadA4)") (class "Default")
      (node (ref "U1") (pin "A4") (pinfunction "PT10A_A4") (pintype "bidirectional+no_connect"))
    )
    (net (code "84") (name "unconnected-(U1B-PT10B-PadC5)") (class "Default")
      (node (ref "U1") (pin "C5") (pinfunction "PT10B_C5") (pintype "bidirectional+no_connect"))
    )
    (net (code "85") (name "unconnected-(U1B-PT12A-PadA3)") (class "Default")
      (node (ref "U1") (pin "A3") (pinfunction "PT12A_A3") (pintype "bidirectional+no_connect"))
    )
    (net (code "86") (name "unconnected-(U1B-PT12B-PadB4)") (class "Default")
      (node (ref "U1") (pin "B4") (pinfunction "PT12B_B4") (pintype "bidirectional+no_connect"))
    )
    (net (code "87") (name "unconnected-(U1B-PT14A-PadD6)") (class "Default")
      (node (ref "U1") (pin "D6") (pinfunction "PT14A_D6") (pintype "bidirectional+no_connect"))
    )
    (net (code "88") (name "unconnected-(U1B-PT14B-PadE7)") (class "Default")
      (node (ref "U1") (pin "E7") (pinfunction "PT14B_E7") (pintype "bidirectional+no_connect"))
    )
    (net (code "89") (name "unconnected-(U1B-PT15A-PadB7)") (class "Default")
      (node (ref "U1") (pin "B7") (pinfunction "PT15A_B7") (pintype "bidirectional+no_connect"))
    )
    (net (code "90") (name "unconnected-(U1B-PT15B-PadC7)") (class "Default")
      (node (ref "U1") (pin "C7") (pinfunction "PT15B_C7") (pintype "bidirectional+no_connect"))
    )
    (net (code "91") (name "unconnected-(U1B-PT16A-PadE6)") (class "Default")
      (node (ref "U1") (pin "E6") (pinfunction "PT16A_E6") (pintype "bidirectional+no_connect"))
    )
    (net (code "92") (name "unconnected-(U1B-PT16B-PadD7)") (class "Default")
      (node (ref "U1") (pin "D7") (pinfunction "PT16B_D7") (pintype "bidirectional+no_connect"))
    )
    (net (code "93") (name "unconnected-(U1B-PT17A-PadF7)") (class "Default")
      (node (ref "U1") (pin "F7") (pinfunction "PT17A_F7") (pintype "bidirectional+no_connect"))
    )
    (net (code "94") (name "unconnected-(U1B-PT17B-PadE8)") (class "Default")
      (node (ref "U1") (pin "E8") (pinfunction "PT17B_E8") (pintype "bidirectional+no_connect"))
    )
    (net (code "95") (name "unconnected-(U1B-PT18A_PCLKT01-PadC8)") (class "Default")
      (node (ref "U1") (pin "C8") (pinfunction "PT18A_PCLKT01_C8") (pintype "bidirectional+no_connect"))
    )
    (net (code "96") (name "unconnected-(U1B-PT18B_PCLKC01-PadA8)") (class "Default")
      (node (ref "U1") (pin "A8") (pinfunction "PT18B_PCLKC01_A8") (pintype "bidirectional+no_connect"))
    )
    (net (code "97") (name "unconnected-(U1B-PT21A-PadD8)") (class "Default")
      (node (ref "U1") (pin "D8") (pinfunction "PT21A_D8") (pintype "bidirectional+no_connect"))
    )
    (net (code "98") (name "unconnected-(U1B-PT21B-PadE9)") (class "Default")
      (node (ref "U1") (pin "E9") (pinfunction "PT21B_E9") (pintype "bidirectional+no_connect"))
    )
    (net (code "99") (name "unconnected-(U1B-PT22A-PadF8)") (class "Default")
      (node (ref "U1") (pin "F8") (pinfunction "PT22A_F8") (pintype "bidirectional+no_connect"))
    )
    (net (code "100") (name "unconnected-(U1B-PT22B-PadD9)") (class "Default")
      (node (ref "U1") (pin "D9") (pinfunction "PT22B_D9") (pintype "bidirectional+no_connect"))
    )
    (net (code "101") (name "unconnected-(U1B-PT22C_SCL_PCLKT00-PadA9)") (class "Default")
      (node (ref "U1") (pin "A9") (pinfunction "PT22C_SCL_PCLKT00_A9") (pintype "bidirectional+no_connect"))
    )
    (net (code "102") (name "unconnected-(U1B-PT22D_SDA_PCLKC00-PadC9)") (class "Default")
      (node (ref "U1") (pin "C9") (pinfunction "PT22D_SDA_PCLKC00_C9") (pintype "bidirectional+no_connect"))
    )
    (net (code "103") (name "unconnected-(U1B-PT25A-PadB9)") (class "Default")
      (node (ref "U1") (pin "B9") (pinfunction "PT25A_B9") (pintype "bidirectional+no_connect"))
    )
    (net (code "104") (name "unconnected-(U1B-PT25B-PadA10)") (class "Default")
      (node (ref "U1") (pin "A10") (pinfunction "PT25B_A10") (pintype "bidirectional+no_connect"))
    )
    (net (code "105") (name "unconnected-(U1B-PT26A-PadF9)") (class "Default")
      (node (ref "U1") (pin "F9") (pinfunction "PT26A_F9") (pintype "bidirectional+no_connect"))
    )
    (net (code "106") (name "unconnected-(U1B-PT26B-PadE11)") (class "Default")
      (node (ref "U1") (pin "E11") (pinfunction "PT26B_E11") (pintype "bidirectional+no_connect"))
    )
    (net (code "107") (name "unconnected-(U1B-PT27A-PadD10)") (class "Default")
      (node (ref "U1") (pin "D10") (pinfunction "PT27A_D10") (pintype "bidirectional+no_connect"))
    )
    (net (code "108") (name "unconnected-(U1B-PT27B-PadE10)") (class "Default")
      (node (ref "U1") (pin "E10") (pinfunction "PT27B_E10") (pintype "bidirectional+no_connect"))
    )
    (net (code "109") (name "unconnected-(U1B-PT27C_JTAGENB-PadC10)") (class "Default")
      (node (ref "U1") (pin "C10") (pinfunction "PT27C_JTAGENB_C10") (pintype "bidirectional+no_connect"))
    )
    (net (code "110") (name "unconnected-(U1B-PT27D_PROGRAMN-PadB10)") (class "Default")
      (node (ref "U1") (pin "B10") (pinfunction "PT27D_PROGRAMN_B10") (pintype "bidirectional+no_connect"))
    )
    (net (code "111") (name "unconnected-(U1B-PT28A-PadA11)") (class "Default")
      (node (ref "U1") (pin "A11") (pinfunction "PT28A_A11") (pintype "bidirectional+no_connect"))
    )
    (net (code "112") (name "unconnected-(U1B-PT28B-PadC11)") (class "Default")
      (node (ref "U1") (pin "C11") (pinfunction "PT28B_C11") (pintype "bidirectional+no_connect"))
    )
    (net (code "113") (name "unconnected-(U1B-PT32A-PadF10)") (class "Default")
      (node (ref "U1") (pin "F10") (pinfunction "PT32A_F10") (pintype "bidirectional+no_connect"))
    )
    (net (code "114") (name "unconnected-(U1B-PT32B-PadD11)") (class "Default")
      (node (ref "U1") (pin "D11") (pinfunction "PT32B_D11") (pintype "bidirectional+no_connect"))
    )
    (net (code "115") (name "unconnected-(U1B-PT33A-PadB11)") (class "Default")
      (node (ref "U1") (pin "B11") (pinfunction "PT33A_B11") (pintype "bidirectional+no_connect"))
    )
    (net (code "116") (name "unconnected-(U1B-PT33B-PadA12)") (class "Default")
      (node (ref "U1") (pin "A12") (pinfunction "PT33B_A12") (pintype "bidirectional+no_connect"))
    )
    (net (code "117") (name "unconnected-(U1B-PT34A-PadB13)") (class "Default")
      (node (ref "U1") (pin "B13") (pinfunction "PT34A_B13") (pintype "bidirectional+no_connect"))
    )
    (net (code "118") (name "unconnected-(U1B-PT34B-PadA14)") (class "Default")
      (node (ref "U1") (pin "A14") (pinfunction "PT34B_A14") (pintype "bidirectional+no_connect"))
    )
    (net (code "119") (name "unconnected-(U1B-PT35A-PadC12)") (class "Default")
      (node (ref "U1") (pin "C12") (pinfunction "PT35A_C12") (pintype "bidirectional+no_connect"))
    )
    (net (code "120") (name "unconnected-(U1B-PT35B-PadB12)") (class "Default")
      (node (ref "U1") (pin "B12") (pinfunction "PT35B_B12") (pintype "bidirectional+no_connect"))
    )
    (net (code "121") (name "unconnected-(U1B-PT36A-PadB14)") (class "Default")
      (node (ref "U1") (pin "B14") (pinfunction "PT36A_B14") (pintype "bidirectional+no_connect"))
    )
    (net (code "122") (name "unconnected-(U1B-PT36B-PadA15)") (class "Default")
      (node (ref "U1") (pin "A15") (pinfunction "PT36B_A15") (pintype "bidirectional+no_connect"))
    )
    (net (code "123") (name "unconnected-(U1C-PR2A_RGPLLTFB-PadD14)") (class "Default")
      (node (ref "U1") (pin "D14") (pinfunction "PR2A_RGPLLTFB_D14") (pintype "bidirectional+no_connect"))
    )
    (net (code "124") (name "unconnected-(U1C-PR2B_RGPLLCFB-PadE15)") (class "Default")
      (node (ref "U1") (pin "E15") (pinfunction "PR2B_RGPLLCFB_E15") (pintype "bidirectional+no_connect"))
    )
    (net (code "125") (name "unconnected-(U1C-PR2C-PadC15)") (class "Default")
      (node (ref "U1") (pin "C15") (pinfunction "PR2C_C15") (pintype "bidirectional+no_connect"))
    )
    (net (code "126") (name "unconnected-(U1C-PR2D-PadB16)") (class "Default")
      (node (ref "U1") (pin "B16") (pinfunction "PR2D_B16") (pintype "bidirectional+no_connect"))
    )
    (net (code "127") (name "unconnected-(U1C-PR3A_RGPLLTIN-PadD16)") (class "Default")
      (node (ref "U1") (pin "D16") (pinfunction "PR3A_RGPLLTIN_D16") (pintype "bidirectional+no_connect"))
    )
    (net (code "128") (name "unconnected-(U1C-PR3B_RGPLLCIN-PadE14)") (class "Default")
      (node (ref "U1") (pin "E14") (pinfunction "PR3B_RGPLLCIN_E14") (pintype "bidirectional+no_connect"))
    )
    (net (code "129") (name "unconnected-(U1C-PR4C-PadC16)") (class "Default")
      (node (ref "U1") (pin "C16") (pinfunction "PR4C_C16") (pintype "bidirectional+no_connect"))
    )
    (net (code "130") (name "unconnected-(U1C-PR4D-PadD15)") (class "Default")
      (node (ref "U1") (pin "D15") (pinfunction "PR4D_D15") (pintype "bidirectional+no_connect"))
    )
    (net (code "131") (name "unconnected-(U1C-PR5A-PadE16)") (class "Default")
      (node (ref "U1") (pin "E16") (pinfunction "PR5A_E16") (pintype "bidirectional+no_connect"))
    )
    (net (code "132") (name "unconnected-(U1C-PR5B-PadF15)") (class "Default")
      (node (ref "U1") (pin "F15") (pinfunction "PR5B_F15") (pintype "bidirectional+no_connect"))
    )
    (net (code "133") (name "unconnected-(U1C-PR6C-PadF13)") (class "Default")
      (node (ref "U1") (pin "F13") (pinfunction "PR6C_F13") (pintype "bidirectional+no_connect"))
    )
    (net (code "134") (name "unconnected-(U1C-PR6D-PadG12)") (class "Default")
      (node (ref "U1") (pin "G12") (pinfunction "PR6D_G12") (pintype "bidirectional+no_connect"))
    )
    (net (code "135") (name "unconnected-(U1C-PR7A-PadF14)") (class "Default")
      (node (ref "U1") (pin "F14") (pinfunction "PR7A_F14") (pintype "bidirectional+no_connect"))
    )
    (net (code "136") (name "unconnected-(U1C-PR7B-PadF16)") (class "Default")
      (node (ref "U1") (pin "F16") (pinfunction "PR7B_F16") (pintype "bidirectional+no_connect"))
    )
    (net (code "137") (name "unconnected-(U1C-PR7C-PadF12)") (class "Default")
      (node (ref "U1") (pin "F12") (pinfunction "PR7C_F12") (pintype "bidirectional+no_connect"))
    )
    (net (code "138") (name "unconnected-(U1C-PR7D-PadG13)") (class "Default")
      (node (ref "U1") (pin "G13") (pinfunction "PR7D_G13") (pintype "bidirectional+no_connect"))
    )
    (net (code "139") (name "unconnected-(U1C-PR9A-PadG15)") (class "Default")
      (node (ref "U1") (pin "G15") (pinfunction "PR9A_G15") (pintype "bidirectional+no_connect"))
    )
    (net (code "140") (name "unconnected-(U1C-PR9B-PadG14)") (class "Default")
      (node (ref "U1") (pin "G14") (pinfunction "PR9B_G14") (pintype "bidirectional+no_connect"))
    )
    (net (code "141") (name "unconnected-(U1C-PR10C-PadG11)") (class "Default")
      (node (ref "U1") (pin "G11") (pinfunction "PR10C_G11") (pintype "bidirectional+no_connect"))
    )
    (net (code "142") (name "unconnected-(U1C-PR10D-PadH12)") (class "Default")
      (node (ref "U1") (pin "H12") (pinfunction "PR10D_H12") (pintype "bidirectional+no_connect"))
    )
    (net (code "143") (name "unconnected-(U1C-PR11A-PadG16)") (class "Default")
      (node (ref "U1") (pin "G16") (pinfunction "PR11A_G16") (pintype "bidirectional+no_connect"))
    )
    (net (code "144") (name "unconnected-(U1C-PR11B-PadH15)") (class "Default")
      (node (ref "U1") (pin "H15") (pinfunction "PR11B_H15") (pintype "bidirectional+no_connect"))
    )
    (net (code "145") (name "unconnected-(U1C-PR11C-PadH13)") (class "Default")
      (node (ref "U1") (pin "H13") (pinfunction "PR11C_H13") (pintype "bidirectional+no_connect"))
    )
    (net (code "146") (name "unconnected-(U1C-PR11D-PadJ12)") (class "Default")
      (node (ref "U1") (pin "J12") (pinfunction "PR11D_J12") (pintype "bidirectional+no_connect"))
    )
    (net (code "147") (name "unconnected-(U1C-PR12A_PCLKT10-PadH14)") (class "Default")
      (node (ref "U1") (pin "H14") (pinfunction "PR12A_PCLKT10_H14") (pintype "bidirectional+no_connect"))
    )
    (net (code "148") (name "unconnected-(U1C-PR12B_PCLKC10-PadH16)") (class "Default")
      (node (ref "U1") (pin "H16") (pinfunction "PR12B_PCLKC10_H16") (pintype "bidirectional+no_connect"))
    )
    (net (code "149") (name "unconnected-(U1C-PR15A-PadJ16)") (class "Default")
      (node (ref "U1") (pin "J16") (pinfunction "PR15A_J16") (pintype "bidirectional+no_connect"))
    )
    (net (code "150") (name "unconnected-(U1C-PR15B-PadJ14)") (class "Default")
      (node (ref "U1") (pin "J14") (pinfunction "PR15B_J14") (pintype "bidirectional+no_connect"))
    )
    (net (code "151") (name "unconnected-(U1C-PR16A-PadJ15)") (class "Default")
      (node (ref "U1") (pin "J15") (pinfunction "PR16A_J15") (pintype "bidirectional+no_connect"))
    )
    (net (code "152") (name "unconnected-(U1C-PR16B-PadK16)") (class "Default")
      (node (ref "U1") (pin "K16") (pinfunction "PR16B_K16") (pintype "bidirectional+no_connect"))
    )
    (net (code "153") (name "unconnected-(U1C-PR16C-PadH11)") (class "Default")
      (node (ref "U1") (pin "H11") (pinfunction "PR16C_H11") (pintype "bidirectional+no_connect"))
    )
    (net (code "154") (name "unconnected-(U1C-PR16D-PadJ13)") (class "Default")
      (node (ref "U1") (pin "J13") (pinfunction "PR16D_J13") (pintype "bidirectional+no_connect"))
    )
    (net (code "155") (name "unconnected-(U1C-PR17A-PadK14)") (class "Default")
      (node (ref "U1") (pin "K14") (pinfunction "PR17A_K14") (pintype "bidirectional+no_connect"))
    )
    (net (code "156") (name "unconnected-(U1C-PR17B-PadK15)") (class "Default")
      (node (ref "U1") (pin "K15") (pinfunction "PR17B_K15") (pintype "bidirectional+no_connect"))
    )
    (net (code "157") (name "unconnected-(U1C-PR17C-PadJ11)") (class "Default")
      (node (ref "U1") (pin "J11") (pinfunction "PR17C_J11") (pintype "bidirectional+no_connect"))
    )
    (net (code "158") (name "unconnected-(U1C-PR17D-PadL12)") (class "Default")
      (node (ref "U1") (pin "L12") (pinfunction "PR17D_L12") (pintype "bidirectional+no_connect"))
    )
    (net (code "159") (name "unconnected-(U1C-PR18A-PadL16)") (class "Default")
      (node (ref "U1") (pin "L16") (pinfunction "PR18A_L16") (pintype "bidirectional+no_connect"))
    )
    (net (code "160") (name "unconnected-(U1C-PR18B-PadL14)") (class "Default")
      (node (ref "U1") (pin "L14") (pinfunction "PR18B_L14") (pintype "bidirectional+no_connect"))
    )
    (net (code "161") (name "unconnected-(U1C-PR19C-PadK13)") (class "Default")
      (node (ref "U1") (pin "K13") (pinfunction "PR19C_K13") (pintype "bidirectional+no_connect"))
    )
    (net (code "162") (name "unconnected-(U1C-PR19D-PadK12)") (class "Default")
      (node (ref "U1") (pin "K12") (pinfunction "PR19D_K12") (pintype "bidirectional+no_connect"))
    )
    (net (code "163") (name "unconnected-(U1C-PR21A-PadL15)") (class "Default")
      (node (ref "U1") (pin "L15") (pinfunction "PR21A_L15") (pintype "bidirectional+no_connect"))
    )
    (net (code "164") (name "unconnected-(U1C-PR21B-PadM16)") (class "Default")
      (node (ref "U1") (pin "M16") (pinfunction "PR21B_M16") (pintype "bidirectional+no_connect"))
    )
    (net (code "165") (name "unconnected-(U1C-PR21C-PadK11)") (class "Default")
      (node (ref "U1") (pin "K11") (pinfunction "PR21C_K11") (pintype "bidirectional+no_connect"))
    )
    (net (code "166") (name "unconnected-(U1C-PR21D-PadL13)") (class "Default")
      (node (ref "U1") (pin "L13") (pinfunction "PR21D_L13") (pintype "bidirectional+no_connect"))
    )
    (net (code "167") (name "unconnected-(U1C-PR23A-PadM14)") (class "Default")
      (node (ref "U1") (pin "M14") (pinfunction "PR23A_M14") (pintype "bidirectional+no_connect"))
    )
    (net (code "168") (name "unconnected-(U1C-PR23B-PadM15)") (class "Default")
      (node (ref "U1") (pin "M15") (pinfunction "PR23B_M15") (pintype "bidirectional+no_connect"))
    )
    (net (code "169") (name "unconnected-(U1C-PR23C-PadN15)") (class "Default")
      (node (ref "U1") (pin "N15") (pinfunction "PR23C_N15") (pintype "bidirectional+no_connect"))
    )
    (net (code "170") (name "unconnected-(U1C-PR23D-PadP16)") (class "Default")
      (node (ref "U1") (pin "P16") (pinfunction "PR23D_P16") (pintype "bidirectional+no_connect"))
    )
    (net (code "171") (name "unconnected-(U1C-PR24A-PadN16)") (class "Default")
      (node (ref "U1") (pin "N16") (pinfunction "PR24A_N16") (pintype "bidirectional+no_connect"))
    )
    (net (code "172") (name "unconnected-(U1C-PR24B-PadN14)") (class "Default")
      (node (ref "U1") (pin "N14") (pinfunction "PR24B_N14") (pintype "bidirectional+no_connect"))
    )
    (net (code "173") (name "unconnected-(U1C-PR25C-PadP15)") (class "Default")
      (node (ref "U1") (pin "P15") (pinfunction "PR25C_P15") (pintype "bidirectional+no_connect"))
    )
    (net (code "174") (name "unconnected-(U1C-PR25D-PadR16)") (class "Default")
      (node (ref "U1") (pin "R16") (pinfunction "PR25D_R16") (pintype "bidirectional+no_connect"))
    )
    (net (code "175") (name "unconnected-(U1D-PB4A-PadP4)") (class "Default")
      (node (ref "U1") (pin "P4") (pinfunction "PB4A_P4") (pintype "bidirectional+no_connect"))
    )
    (net (code "176") (name "unconnected-(U1D-PB6B-PadP5)") (class "Default")
      (node (ref "U1") (pin "P5") (pinfunction "PB6B_P5") (pintype "bidirectional+no_connect"))
    )
    (net (code "177") (name "unconnected-(U1D-PB10A-PadN6)") (class "Default")
      (node (ref "U1") (pin "N6") (pinfunction "PB10A_N6") (pintype "bidirectional+no_connect"))
    )
    (net (code "178") (name "unconnected-(U1D-PB10B-PadL7)") (class "Default")
      (node (ref "U1") (pin "L7") (pinfunction "PB10B_L7") (pintype "bidirectional+no_connect"))
    )
    (net (code "179") (name "unconnected-(U1D-PB12A_MCLK_CCLK-PadP6)") (class "Default")
      (node (ref "U1") (pin "P6") (pinfunction "PB12A_MCLK_CCLK_P6") (pintype "bidirectional+no_connect"))
    )
    (net (code "180") (name "unconnected-(U1D-PB13A-PadR7)") (class "Default")
      (node (ref "U1") (pin "R7") (pinfunction "PB13A_R7") (pintype "bidirectional+no_connect"))
    )
    (net (code "181") (name "unconnected-(U1D-PB13B-PadP7)") (class "Default")
      (node (ref "U1") (pin "P7") (pinfunction "PB13B_P7") (pintype "bidirectional+no_connect"))
    )
    (net (code "182") (name "unconnected-(U1D-PB13C-PadM7)") (class "Default")
      (node (ref "U1") (pin "M7") (pinfunction "PB13C_M7") (pintype "bidirectional+no_connect"))
    )
    (net (code "183") (name "unconnected-(U1D-PB13D-PadN7)") (class "Default")
      (node (ref "U1") (pin "N7") (pinfunction "PB13D_N7") (pintype "bidirectional+no_connect"))
    )
    (net (code "184") (name "unconnected-(U1D-PB15A-PadM6)") (class "Default")
      (node (ref "U1") (pin "M6") (pinfunction "PB15A_M6") (pintype "bidirectional+no_connect"))
    )
    (net (code "185") (name "unconnected-(U1D-PB15B-PadL8)") (class "Default")
      (node (ref "U1") (pin "L8") (pinfunction "PB15B_L8") (pintype "bidirectional+no_connect"))
    )
    (net (code "186") (name "unconnected-(U1D-PB18A-PadP8)") (class "Default")
      (node (ref "U1") (pin "P8") (pinfunction "PB18A_P8") (pintype "bidirectional+no_connect"))
    )
    (net (code "187") (name "unconnected-(U1D-PB18C-PadN8)") (class "Default")
      (node (ref "U1") (pin "N8") (pinfunction "PB18C_N8") (pintype "bidirectional+no_connect"))
    )
    (net (code "188") (name "unconnected-(U1D-PB18D-PadL9)") (class "Default")
      (node (ref "U1") (pin "L9") (pinfunction "PB18D_L9") (pintype "bidirectional+no_connect"))
    )
    (net (code "189") (name "unconnected-(U1D-PB21A-PadM8)") (class "Default")
      (node (ref "U1") (pin "M8") (pinfunction "PB21A_M8") (pintype "bidirectional+no_connect"))
    )
    (net (code "190") (name "unconnected-(U1D-PB21B-PadN9)") (class "Default")
      (node (ref "U1") (pin "N9") (pinfunction "PB21B_N9") (pintype "bidirectional+no_connect"))
    )
    (net (code "191") (name "unconnected-(U1D-PB23B_PCLKC21-PadP9)") (class "Default")
      (node (ref "U1") (pin "P9") (pinfunction "PB23B_PCLKC21_P9") (pintype "bidirectional+no_connect"))
    )
    (net (code "192") (name "unconnected-(U1D-PB26C-PadM9)") (class "Default")
      (node (ref "U1") (pin "M9") (pinfunction "PB26C_M9") (pintype "bidirectional+no_connect"))
    )
    (net (code "193") (name "unconnected-(U1D-PB26D-PadL10)") (class "Default")
      (node (ref "U1") (pin "L10") (pinfunction "PB26D_L10") (pintype "bidirectional+no_connect"))
    )
    (net (code "194") (name "unconnected-(U1D-PB28A-PadN10)") (class "Default")
      (node (ref "U1") (pin "N10") (pinfunction "PB28A_N10") (pintype "bidirectional+no_connect"))
    )
    (net (code "195") (name "unconnected-(U1D-PB28B-PadM11)") (class "Default")
      (node (ref "U1") (pin "M11") (pinfunction "PB28B_M11") (pintype "bidirectional+no_connect"))
    )
    (net (code "196") (name "unconnected-(U1D-PB29A-PadP10)") (class "Default")
      (node (ref "U1") (pin "P10") (pinfunction "PB29A_P10") (pintype "bidirectional+no_connect"))
    )
    (net (code "197") (name "unconnected-(U1D-PB31B-PadP11)") (class "Default")
      (node (ref "U1") (pin "P11") (pinfunction "PB31B_P11") (pintype "bidirectional+no_connect"))
    )
    (net (code "198") (name "unconnected-(U1D-PB31C-PadM10)") (class "Default")
      (node (ref "U1") (pin "M10") (pinfunction "PB31C_M10") (pintype "bidirectional+no_connect"))
    )
    (net (code "199") (name "unconnected-(U1D-PB31D-PadN11)") (class "Default")
      (node (ref "U1") (pin "N11") (pinfunction "PB31D_N11") (pintype "bidirectional+no_connect"))
    )
    (net (code "200") (name "unconnected-(U1D-PB37A-PadP12)") (class "Default")
      (node (ref "U1") (pin "P12") (pinfunction "PB37A_P12") (pintype "bidirectional+no_connect"))
    )
    (net (code "201") (name "unconnected-(U1E-PL19B-PadL3)") (class "Default")
      (node (ref "U1") (pin "L3") (pinfunction "PL19B_L3") (pintype "bidirectional+no_connect"))
    )
    (net (code "202") (name "unconnected-(U1E-PL19C-PadK4)") (class "Default")
      (node (ref "U1") (pin "K4") (pinfunction "PL19C_K4") (pintype "bidirectional+no_connect"))
    )
    (net (code "203") (name "unconnected-(U1E-PL19D-PadL5)") (class "Default")
      (node (ref "U1") (pin "L5") (pinfunction "PL19D_L5") (pintype "bidirectional+no_connect"))
    )
    (net (code "204") (name "unconnected-(U1E-PL21C-PadK5)") (class "Default")
      (node (ref "U1") (pin "K5") (pinfunction "PL21C_K5") (pintype "bidirectional+no_connect"))
    )
    (net (code "205") (name "unconnected-(U1E-PL21D-PadL4)") (class "Default")
      (node (ref "U1") (pin "L4") (pinfunction "PL21D_L4") (pintype "bidirectional+no_connect"))
    )
    (net (code "206") (name "unconnected-(U1E-PL23C-PadN2)") (class "Default")
      (node (ref "U1") (pin "N2") (pinfunction "PL23C_N2") (pintype "bidirectional+no_connect"))
    )
    (net (code "207") (name "unconnected-(U1E-PL23D-PadP1)") (class "Default")
      (node (ref "U1") (pin "P1") (pinfunction "PL23D_P1") (pintype "bidirectional+no_connect"))
    )
    (net (code "208") (name "unconnected-(U1E-PL24A-PadM3)") (class "Default")
      (node (ref "U1") (pin "M3") (pinfunction "PL24A_M3") (pintype "bidirectional+no_connect"))
    )
    (net (code "209") (name "unconnected-(U1E-PL24B-PadN1)") (class "Default")
      (node (ref "U1") (pin "N1") (pinfunction "PL24B_N1") (pintype "bidirectional+no_connect"))
    )
    (net (code "210") (name "unconnected-(U1E-PL25B-PadN3)") (class "Default")
      (node (ref "U1") (pin "N3") (pinfunction "PL25B_N3") (pintype "bidirectional+no_connect"))
    )
    (net (code "211") (name "unconnected-(U1E-PL25C-PadR1)") (class "Default")
      (node (ref "U1") (pin "R1") (pinfunction "PL25C_R1") (pintype "bidirectional+no_connect"))
    )
    (net (code "212") (name "unconnected-(U1E-PL25D-PadP2)") (class "Default")
      (node (ref "U1") (pin "P2") (pinfunction "PL25D_P2") (pintype "bidirectional+no_connect"))
    )
    (net (code "213") (name "unconnected-(U1F-PL10A-PadG1)") (class "Default")
      (node (ref "U1") (pin "G1") (pinfunction "PL10A_G1") (pintype "bidirectional+no_connect"))
    )
    (net (code "214") (name "unconnected-(U1F-PL10B-PadH2)") (class "Default")
      (node (ref "U1") (pin "H2") (pinfunction "PL10B_H2") (pintype "bidirectional+no_connect"))
    )
    (net (code "215") (name "unconnected-(U1F-PL10C-PadH4)") (class "Default")
      (node (ref "U1") (pin "H4") (pinfunction "PL10C_H4") (pintype "bidirectional+no_connect"))
    )
    (net (code "216") (name "unconnected-(U1F-PL10D-PadJ6)") (class "Default")
      (node (ref "U1") (pin "J6") (pinfunction "PL10D_J6") (pintype "bidirectional+no_connect"))
    )
    (net (code "217") (name "unconnected-(U1F-PL11A-PadH3)") (class "Default")
      (node (ref "U1") (pin "H3") (pinfunction "PL11A_H3") (pintype "bidirectional+no_connect"))
    )
    (net (code "218") (name "unconnected-(U1F-PL11B-PadH1)") (class "Default")
      (node (ref "U1") (pin "H1") (pinfunction "PL11B_H1") (pintype "bidirectional+no_connect"))
    )
    (net (code "219") (name "unconnected-(U1F-PL12A_PCLKT40-PadJ1)") (class "Default")
      (node (ref "U1") (pin "J1") (pinfunction "PL12A_PCLKT40_J1") (pintype "bidirectional+no_connect"))
    )
    (net (code "220") (name "unconnected-(U1F-PL12B_PCLKC40-PadJ3)") (class "Default")
      (node (ref "U1") (pin "J3") (pinfunction "PL12B_PCLKC40_J3") (pintype "bidirectional+no_connect"))
    )
    (net (code "221") (name "unconnected-(U1F-PL15A-PadJ2)") (class "Default")
      (node (ref "U1") (pin "J2") (pinfunction "PL15A_J2") (pintype "bidirectional+no_connect"))
    )
    (net (code "222") (name "unconnected-(U1F-PL15B-PadK1)") (class "Default")
      (node (ref "U1") (pin "K1") (pinfunction "PL15B_K1") (pintype "bidirectional+no_connect"))
    )
    (net (code "223") (name "unconnected-(U1F-PL15C-PadH5)") (class "Default")
      (node (ref "U1") (pin "H5") (pinfunction "PL15C_H5") (pintype "bidirectional+no_connect"))
    )
    (net (code "224") (name "unconnected-(U1F-PL15D-PadJ4)") (class "Default")
      (node (ref "U1") (pin "J4") (pinfunction "PL15D_J4") (pintype "bidirectional+no_connect"))
    )
    (net (code "225") (name "unconnected-(U1F-PL16C-PadJ5)") (class "Default")
      (node (ref "U1") (pin "J5") (pinfunction "PL16C_J5") (pintype "bidirectional+no_connect"))
    )
    (net (code "226") (name "unconnected-(U1F-PL16D-PadK6)") (class "Default")
      (node (ref "U1") (pin "K6") (pinfunction "PL16D_K6") (pintype "bidirectional+no_connect"))
    )
    (net (code "227") (name "unconnected-(U1F-PL17A-PadK3)") (class "Default")
      (node (ref "U1") (pin "K3") (pinfunction "PL17A_K3") (pintype "bidirectional+no_connect"))
    )
    (net (code "228") (name "unconnected-(U1F-PL17B-PadK2)") (class "Default")
      (node (ref "U1") (pin "K2") (pinfunction "PL17B_K2") (pintype "bidirectional+no_connect"))
    )
    (net (code "229") (name "unconnected-(U1G-PL2C-PadB1)") (class "Default")
      (node (ref "U1") (pin "B1") (pinfunction "PL2C_B1") (pintype "bidirectional+no_connect"))
    )
    (net (code "230") (name "unconnected-(U1G-PL2D-PadC2)") (class "Default")
      (node (ref "U1") (pin "C2") (pinfunction "PL2D_C2") (pintype "bidirectional+no_connect"))
    )
    (net (code "231") (name "unconnected-(U1G-PL3A_LGPLLTFB-PadD3)") (class "Default")
      (node (ref "U1") (pin "D3") (pinfunction "PL3A_LGPLLTFB_D3") (pintype "bidirectional+no_connect"))
    )
    (net (code "232") (name "unconnected-(U1G-PL3B_LGPLLCFB-PadD1)") (class "Default")
      (node (ref "U1") (pin "D1") (pinfunction "PL3B_LGPLLCFB_D1") (pintype "bidirectional+no_connect"))
    )
    (net (code "233") (name "unconnected-(U1G-PL4B_LGPLLCIN-PadE3)") (class "Default")
      (node (ref "U1") (pin "E3") (pinfunction "PL4B_LGPLLCIN_E3") (pintype "bidirectional+no_connect"))
    )
    (net (code "234") (name "unconnected-(U1G-PL4C-PadC1)") (class "Default")
      (node (ref "U1") (pin "C1") (pinfunction "PL4C_C1") (pintype "bidirectional+no_connect"))
    )
    (net (code "235") (name "unconnected-(U1G-PL4D-PadD2)") (class "Default")
      (node (ref "U1") (pin "D2") (pinfunction "PL4D_D2") (pintype "bidirectional+no_connect"))
    )
    (net (code "236") (name "unconnected-(U1G-PL6A_PCLKT50-PadE1)") (class "Default")
      (node (ref "U1") (pin "E1") (pinfunction "PL6A_PCLKT50_E1") (pintype "bidirectional+no_connect"))
    )
    (net (code "237") (name "unconnected-(U1G-PL6B_PCLKC50-PadF2)") (class "Default")
      (node (ref "U1") (pin "F2") (pinfunction "PL6B_PCLKC50_F2") (pintype "bidirectional+no_connect"))
    )
    (net (code "238") (name "unconnected-(U1G-PL6C-PadF4)") (class "Default")
      (node (ref "U1") (pin "F4") (pinfunction "PL6C_F4") (pintype "bidirectional+no_connect"))
    )
    (net (code "239") (name "unconnected-(U1G-PL6D-PadG6)") (class "Default")
      (node (ref "U1") (pin "G6") (pinfunction "PL6D_G6") (pintype "bidirectional+no_connect"))
    )
    (net (code "240") (name "unconnected-(U1G-PL7C-PadG5)") (class "Default")
      (node (ref "U1") (pin "G5") (pinfunction "PL7C_G5") (pintype "bidirectional+no_connect"))
    )
    (net (code "241") (name "unconnected-(U1G-PL7D-PadG4)") (class "Default")
      (node (ref "U1") (pin "G4") (pinfunction "PL7D_G4") (pintype "bidirectional+no_connect"))
    )
    (net (code "242") (name "unconnected-(U1G-PL8A-PadF3)") (class "Default")
      (node (ref "U1") (pin "F3") (pinfunction "PL8A_F3") (pintype "bidirectional+no_connect"))
    )
    (net (code "243") (name "unconnected-(U1G-PL8B-PadF1)") (class "Default")
      (node (ref "U1") (pin "F1") (pinfunction "PL8B_F1") (pintype "bidirectional+no_connect"))
    )
    (net (code "244") (name "unconnected-(U1G-PL9A-PadG2)") (class "Default")
      (node (ref "U1") (pin "G2") (pinfunction "PL9A_G2") (pintype "bidirectional+no_connect"))
    )
    (net (code "245") (name "unconnected-(U1G-PL9B-PadG3)") (class "Default")
      (node (ref "U1") (pin "G3") (pinfunction "PL9B_G3") (pintype "bidirectional+no_connect"))
    )
    (net (code "246") (name "unconnected-(U1G-PL9C-PadF5)") (class "Default")
      (node (ref "U1") (pin "F5") (pinfunction "PL9C_F5") (pintype "bidirectional+no_connect"))
    )
    (net (code "247") (name "unconnected-(U1G-PL9D-PadH6)") (class "Default")
      (node (ref "U1") (pin "H6") (pinfunction "PL9D_H6") (pintype "bidirectional+no_connect"))
    )
  )
)
